# Temp_SMD.net
KiCad netlist of a schematic drawn in EAGLE
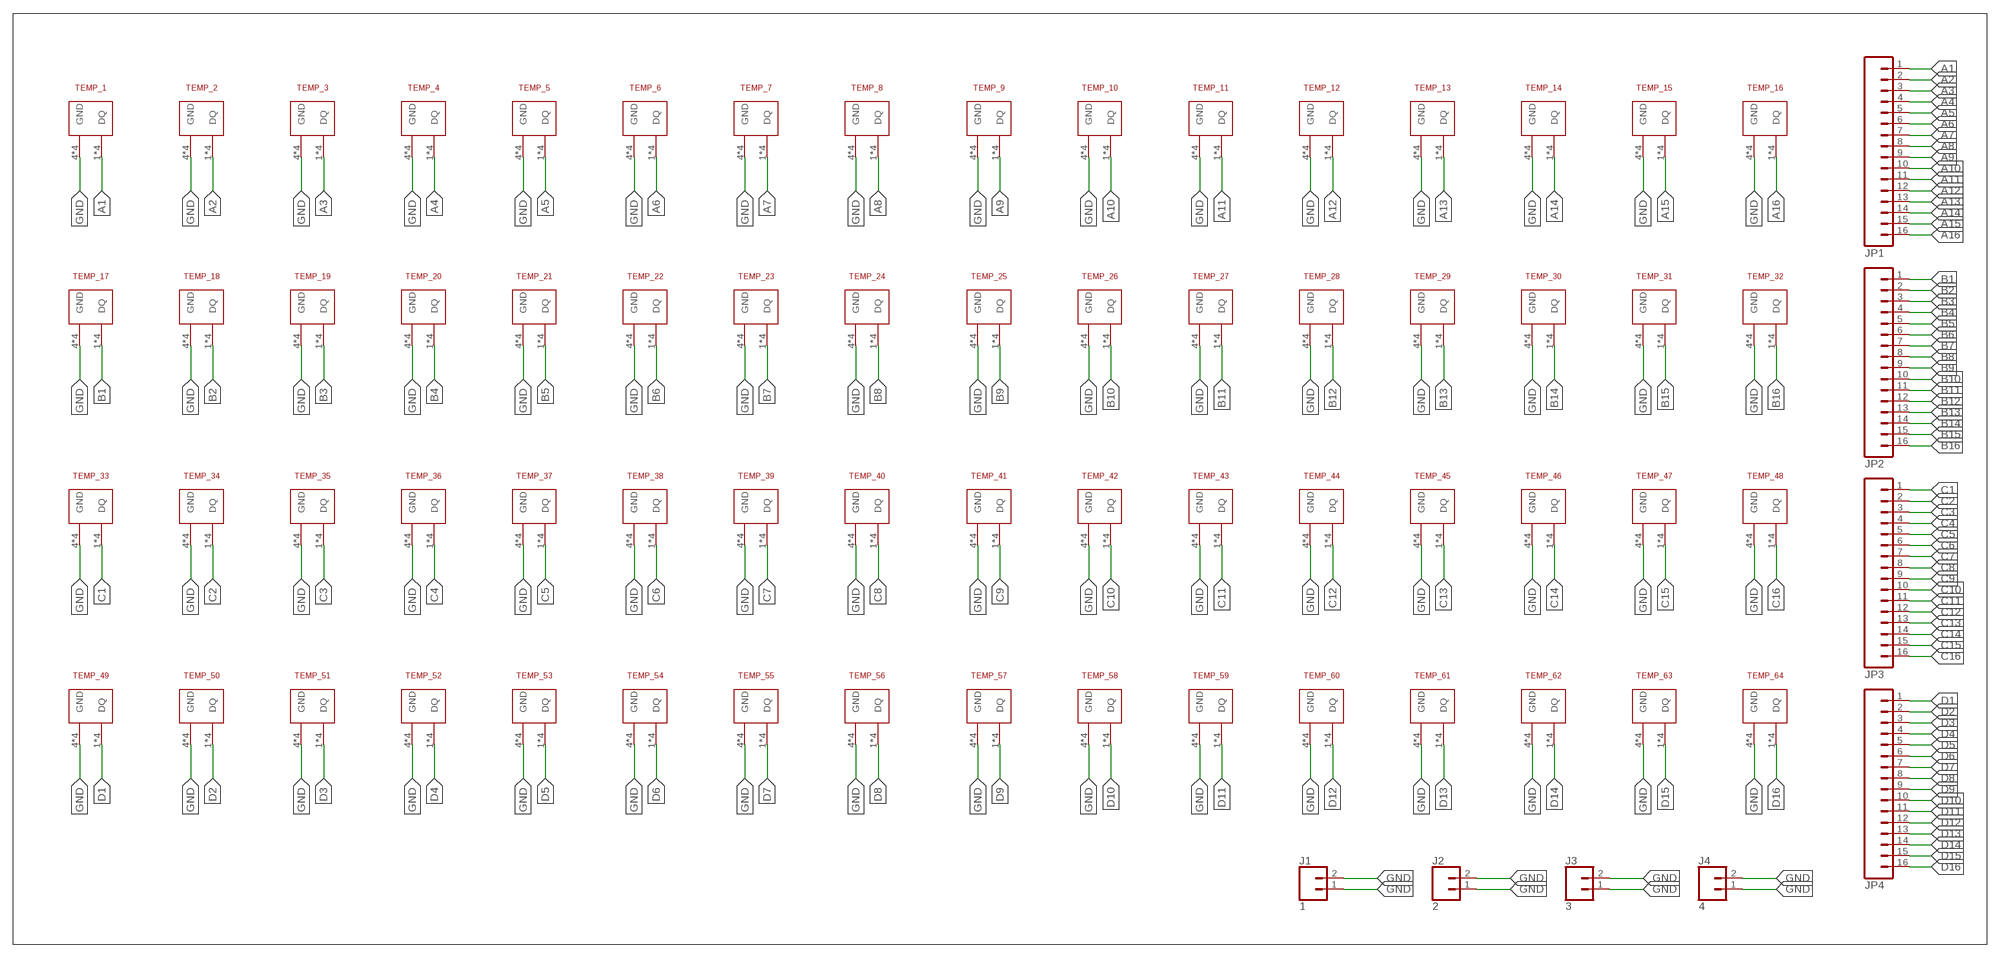
[diagram p0: schematic, sheet 1]

(export (version "E")
  (design (tool "Eeschema 10.0.6"))
  (components
    (comp (ref "J1")
      (value "1")
      (footprint "eagle-import:1X02")
      (libsource (lib "eagle-import") (part "CONN_02"))
    )
    (comp (ref "J2")
      (value "2")
      (footprint "eagle-import:1X02")
      (libsource (lib "eagle-import") (part "CONN_02"))
    )
    (comp (ref "J3")
      (value "3")
      (footprint "eagle-import:1X02")
      (libsource (lib "eagle-import") (part "CONN_02"))
    )
    (comp (ref "J4")
      (value "4")
      (footprint "eagle-import:1X02")
      (libsource (lib "eagle-import") (part "CONN_02"))
    )
    (comp (ref "JP1")
      (value "M16PTH")
      (footprint "eagle-import:1X16")
      (libsource (lib "eagle-import") (part "M16PTH"))
    )
    (comp (ref "JP2")
      (value "M16PTH")
      (footprint "eagle-import:1X16")
      (libsource (lib "eagle-import") (part "M16PTH"))
    )
    (comp (ref "JP3")
      (value "M16PTH")
      (footprint "eagle-import:1X16")
      (libsource (lib "eagle-import") (part "M16PTH"))
    )
    (comp (ref "JP4")
      (value "M16PTH")
      (footprint "eagle-import:1X16")
      (libsource (lib "eagle-import") (part "M16PTH"))
    )
    (comp (ref "TEMP_1")
      (value "SMD_TEMP")
      (footprint "eagle-import:SMD_TEMP")
      (libsource (lib "eagle-import") (part "SMD_TEMP"))
    )
    (comp (ref "TEMP_2")
      (value "SMD_TEMP")
      (footprint "eagle-import:SMD_TEMP")
      (libsource (lib "eagle-import") (part "SMD_TEMP"))
    )
    (comp (ref "TEMP_3")
      (value "SMD_TEMP")
      (footprint "eagle-import:SMD_TEMP")
      (libsource (lib "eagle-import") (part "SMD_TEMP"))
    )
    (comp (ref "TEMP_4")
      (value "SMD_TEMP")
      (footprint "eagle-import:SMD_TEMP")
      (libsource (lib "eagle-import") (part "SMD_TEMP"))
    )
    (comp (ref "TEMP_5")
      (value "SMD_TEMP")
      (footprint "eagle-import:SMD_TEMP")
      (libsource (lib "eagle-import") (part "SMD_TEMP"))
    )
    (comp (ref "TEMP_6")
      (value "SMD_TEMP")
      (footprint "eagle-import:SMD_TEMP")
      (libsource (lib "eagle-import") (part "SMD_TEMP"))
    )
    (comp (ref "TEMP_7")
      (value "SMD_TEMP")
      (footprint "eagle-import:SMD_TEMP")
      (libsource (lib "eagle-import") (part "SMD_TEMP"))
    )
    (comp (ref "TEMP_8")
      (value "SMD_TEMP")
      (footprint "eagle-import:SMD_TEMP")
      (libsource (lib "eagle-import") (part "SMD_TEMP"))
    )
    (comp (ref "TEMP_9")
      (value "SMD_TEMP")
      (footprint "eagle-import:SMD_TEMP")
      (libsource (lib "eagle-import") (part "SMD_TEMP"))
    )
    (comp (ref "TEMP_10")
      (value "SMD_TEMP")
      (footprint "eagle-import:SMD_TEMP")
      (libsource (lib "eagle-import") (part "SMD_TEMP"))
    )
    (comp (ref "TEMP_11")
      (value "SMD_TEMP")
      (footprint "eagle-import:SMD_TEMP")
      (libsource (lib "eagle-import") (part "SMD_TEMP"))
    )
    (comp (ref "TEMP_12")
      (value "SMD_TEMP")
      (footprint "eagle-import:SMD_TEMP")
      (libsource (lib "eagle-import") (part "SMD_TEMP"))
    )
    (comp (ref "TEMP_13")
      (value "SMD_TEMP")
      (footprint "eagle-import:SMD_TEMP")
      (libsource (lib "eagle-import") (part "SMD_TEMP"))
    )
    (comp (ref "TEMP_14")
      (value "SMD_TEMP")
      (footprint "eagle-import:SMD_TEMP")
      (libsource (lib "eagle-import") (part "SMD_TEMP"))
    )
    (comp (ref "TEMP_15")
      (value "SMD_TEMP")
      (footprint "eagle-import:SMD_TEMP")
      (libsource (lib "eagle-import") (part "SMD_TEMP"))
    )
    (comp (ref "TEMP_16")
      (value "SMD_TEMP")
      (footprint "eagle-import:SMD_TEMP")
      (libsource (lib "eagle-import") (part "SMD_TEMP"))
    )
    (comp (ref "TEMP_17")
      (value "SMD_TEMP")
      (footprint "eagle-import:SMD_TEMP")
      (libsource (lib "eagle-import") (part "SMD_TEMP"))
    )
    (comp (ref "TEMP_18")
      (value "SMD_TEMP")
      (footprint "eagle-import:SMD_TEMP")
      (libsource (lib "eagle-import") (part "SMD_TEMP"))
    )
    (comp (ref "TEMP_19")
      (value "SMD_TEMP")
      (footprint "eagle-import:SMD_TEMP")
      (libsource (lib "eagle-import") (part "SMD_TEMP"))
    )
    (comp (ref "TEMP_20")
      (value "SMD_TEMP")
      (footprint "eagle-import:SMD_TEMP")
      (libsource (lib "eagle-import") (part "SMD_TEMP"))
    )
    (comp (ref "TEMP_21")
      (value "SMD_TEMP")
      (footprint "eagle-import:SMD_TEMP")
      (libsource (lib "eagle-import") (part "SMD_TEMP"))
    )
    (comp (ref "TEMP_22")
      (value "SMD_TEMP")
      (footprint "eagle-import:SMD_TEMP")
      (libsource (lib "eagle-import") (part "SMD_TEMP"))
    )
    (comp (ref "TEMP_23")
      (value "SMD_TEMP")
      (footprint "eagle-import:SMD_TEMP")
      (libsource (lib "eagle-import") (part "SMD_TEMP"))
    )
    (comp (ref "TEMP_24")
      (value "SMD_TEMP")
      (footprint "eagle-import:SMD_TEMP")
      (libsource (lib "eagle-import") (part "SMD_TEMP"))
    )
    (comp (ref "TEMP_25")
      (value "SMD_TEMP")
      (footprint "eagle-import:SMD_TEMP")
      (libsource (lib "eagle-import") (part "SMD_TEMP"))
    )
    (comp (ref "TEMP_26")
      (value "SMD_TEMP")
      (footprint "eagle-import:SMD_TEMP")
      (libsource (lib "eagle-import") (part "SMD_TEMP"))
    )
    (comp (ref "TEMP_27")
      (value "SMD_TEMP")
      (footprint "eagle-import:SMD_TEMP")
      (libsource (lib "eagle-import") (part "SMD_TEMP"))
    )
    (comp (ref "TEMP_28")
      (value "SMD_TEMP")
      (footprint "eagle-import:SMD_TEMP")
      (libsource (lib "eagle-import") (part "SMD_TEMP"))
    )
    (comp (ref "TEMP_29")
      (value "SMD_TEMP")
      (footprint "eagle-import:SMD_TEMP")
      (libsource (lib "eagle-import") (part "SMD_TEMP"))
    )
    (comp (ref "TEMP_30")
      (value "SMD_TEMP")
      (footprint "eagle-import:SMD_TEMP")
      (libsource (lib "eagle-import") (part "SMD_TEMP"))
    )
    (comp (ref "TEMP_31")
      (value "SMD_TEMP")
      (footprint "eagle-import:SMD_TEMP")
      (libsource (lib "eagle-import") (part "SMD_TEMP"))
    )
    (comp (ref "TEMP_32")
      (value "SMD_TEMP")
      (footprint "eagle-import:SMD_TEMP")
      (libsource (lib "eagle-import") (part "SMD_TEMP"))
    )
    (comp (ref "TEMP_33")
      (value "SMD_TEMP")
      (footprint "eagle-import:SMD_TEMP")
      (libsource (lib "eagle-import") (part "SMD_TEMP"))
    )
    (comp (ref "TEMP_34")
      (value "SMD_TEMP")
      (footprint "eagle-import:SMD_TEMP")
      (libsource (lib "eagle-import") (part "SMD_TEMP"))
    )
    (comp (ref "TEMP_35")
      (value "SMD_TEMP")
      (footprint "eagle-import:SMD_TEMP")
      (libsource (lib "eagle-import") (part "SMD_TEMP"))
    )
    (comp (ref "TEMP_36")
      (value "SMD_TEMP")
      (footprint "eagle-import:SMD_TEMP")
      (libsource (lib "eagle-import") (part "SMD_TEMP"))
    )
    (comp (ref "TEMP_37")
      (value "SMD_TEMP")
      (footprint "eagle-import:SMD_TEMP")
      (libsource (lib "eagle-import") (part "SMD_TEMP"))
    )
    (comp (ref "TEMP_38")
      (value "SMD_TEMP")
      (footprint "eagle-import:SMD_TEMP")
      (libsource (lib "eagle-import") (part "SMD_TEMP"))
    )
    (comp (ref "TEMP_39")
      (value "SMD_TEMP")
      (footprint "eagle-import:SMD_TEMP")
      (libsource (lib "eagle-import") (part "SMD_TEMP"))
    )
    (comp (ref "TEMP_40")
      (value "SMD_TEMP")
      (footprint "eagle-import:SMD_TEMP")
      (libsource (lib "eagle-import") (part "SMD_TEMP"))
    )
    (comp (ref "TEMP_41")
      (value "SMD_TEMP")
      (footprint "eagle-import:SMD_TEMP")
      (libsource (lib "eagle-import") (part "SMD_TEMP"))
    )
    (comp (ref "TEMP_42")
      (value "SMD_TEMP")
      (footprint "eagle-import:SMD_TEMP")
      (libsource (lib "eagle-import") (part "SMD_TEMP"))
    )
    (comp (ref "TEMP_43")
      (value "SMD_TEMP")
      (footprint "eagle-import:SMD_TEMP")
      (libsource (lib "eagle-import") (part "SMD_TEMP"))
    )
    (comp (ref "TEMP_44")
      (value "SMD_TEMP")
      (footprint "eagle-import:SMD_TEMP")
      (libsource (lib "eagle-import") (part "SMD_TEMP"))
    )
    (comp (ref "TEMP_45")
      (value "SMD_TEMP")
      (footprint "eagle-import:SMD_TEMP")
      (libsource (lib "eagle-import") (part "SMD_TEMP"))
    )
    (comp (ref "TEMP_46")
      (value "SMD_TEMP")
      (footprint "eagle-import:SMD_TEMP")
      (libsource (lib "eagle-import") (part "SMD_TEMP"))
    )
    (comp (ref "TEMP_47")
      (value "SMD_TEMP")
      (footprint "eagle-import:SMD_TEMP")
      (libsource (lib "eagle-import") (part "SMD_TEMP"))
    )
    (comp (ref "TEMP_48")
      (value "SMD_TEMP")
      (footprint "eagle-import:SMD_TEMP")
      (libsource (lib "eagle-import") (part "SMD_TEMP"))
    )
    (comp (ref "TEMP_49")
      (value "SMD_TEMP")
      (footprint "eagle-import:SMD_TEMP")
      (libsource (lib "eagle-import") (part "SMD_TEMP"))
    )
    (comp (ref "TEMP_50")
      (value "SMD_TEMP")
      (footprint "eagle-import:SMD_TEMP")
      (libsource (lib "eagle-import") (part "SMD_TEMP"))
    )
    (comp (ref "TEMP_51")
      (value "SMD_TEMP")
      (footprint "eagle-import:SMD_TEMP")
      (libsource (lib "eagle-import") (part "SMD_TEMP"))
    )
    (comp (ref "TEMP_52")
      (value "SMD_TEMP")
      (footprint "eagle-import:SMD_TEMP")
      (libsource (lib "eagle-import") (part "SMD_TEMP"))
    )
    (comp (ref "TEMP_53")
      (value "SMD_TEMP")
      (footprint "eagle-import:SMD_TEMP")
      (libsource (lib "eagle-import") (part "SMD_TEMP"))
    )
    (comp (ref "TEMP_54")
      (value "SMD_TEMP")
      (footprint "eagle-import:SMD_TEMP")
      (libsource (lib "eagle-import") (part "SMD_TEMP"))
    )
    (comp (ref "TEMP_55")
      (value "SMD_TEMP")
      (footprint "eagle-import:SMD_TEMP")
      (libsource (lib "eagle-import") (part "SMD_TEMP"))
    )
    (comp (ref "TEMP_56")
      (value "SMD_TEMP")
      (footprint "eagle-import:SMD_TEMP")
      (libsource (lib "eagle-import") (part "SMD_TEMP"))
    )
    (comp (ref "TEMP_57")
      (value "SMD_TEMP")
      (footprint "eagle-import:SMD_TEMP")
      (libsource (lib "eagle-import") (part "SMD_TEMP"))
    )
    (comp (ref "TEMP_58")
      (value "SMD_TEMP")
      (footprint "eagle-import:SMD_TEMP")
      (libsource (lib "eagle-import") (part "SMD_TEMP"))
    )
    (comp (ref "TEMP_59")
      (value "SMD_TEMP")
      (footprint "eagle-import:SMD_TEMP")
      (libsource (lib "eagle-import") (part "SMD_TEMP"))
    )
    (comp (ref "TEMP_60")
      (value "SMD_TEMP")
      (footprint "eagle-import:SMD_TEMP")
      (libsource (lib "eagle-import") (part "SMD_TEMP"))
    )
    (comp (ref "TEMP_61")
      (value "SMD_TEMP")
      (footprint "eagle-import:SMD_TEMP")
      (libsource (lib "eagle-import") (part "SMD_TEMP"))
    )
    (comp (ref "TEMP_62")
      (value "SMD_TEMP")
      (footprint "eagle-import:SMD_TEMP")
      (libsource (lib "eagle-import") (part "SMD_TEMP"))
    )
    (comp (ref "TEMP_63")
      (value "SMD_TEMP")
      (footprint "eagle-import:SMD_TEMP")
      (libsource (lib "eagle-import") (part "SMD_TEMP"))
    )
    (comp (ref "TEMP_64")
      (value "SMD_TEMP")
      (footprint "eagle-import:SMD_TEMP")
      (libsource (lib "eagle-import") (part "SMD_TEMP"))
    )
  )
  (nets
    (net (code "1") (name "A1") (class "Default")
      (node (ref "JP1") (pin "1") (pinfunction "1_1") (pintype "passive"))
      (node (ref "TEMP_1") (pin "1") (pinfunction "DQ_1") (pintype "bidirectional"))
      (node (ref "TEMP_1") (pin "DQ") (pinfunction "DQ_DQ") (pintype "bidirectional"))
      (node (ref "TEMP_1") (pin "DQ1") (pinfunction "DQ_DQ1") (pintype "bidirectional"))
      (node (ref "TEMP_1") (pin "DQ2") (pinfunction "DQ_DQ2") (pintype "bidirectional"))
    )
    (net (code "2") (name "A2") (class "Default")
      (node (ref "JP1") (pin "2") (pinfunction "2_2") (pintype "passive"))
      (node (ref "TEMP_2") (pin "1") (pinfunction "DQ_1") (pintype "bidirectional"))
      (node (ref "TEMP_2") (pin "DQ") (pinfunction "DQ_DQ") (pintype "bidirectional"))
      (node (ref "TEMP_2") (pin "DQ1") (pinfunction "DQ_DQ1") (pintype "bidirectional"))
      (node (ref "TEMP_2") (pin "DQ2") (pinfunction "DQ_DQ2") (pintype "bidirectional"))
    )
    (net (code "3") (name "A3") (class "Default")
      (node (ref "JP1") (pin "3") (pinfunction "3_3") (pintype "passive"))
      (node (ref "TEMP_3") (pin "1") (pinfunction "DQ_1") (pintype "bidirectional"))
      (node (ref "TEMP_3") (pin "DQ") (pinfunction "DQ_DQ") (pintype "bidirectional"))
      (node (ref "TEMP_3") (pin "DQ1") (pinfunction "DQ_DQ1") (pintype "bidirectional"))
      (node (ref "TEMP_3") (pin "DQ2") (pinfunction "DQ_DQ2") (pintype "bidirectional"))
    )
    (net (code "4") (name "A4") (class "Default")
      (node (ref "JP1") (pin "4") (pinfunction "4_4") (pintype "passive"))
      (node (ref "TEMP_4") (pin "1") (pinfunction "DQ_1") (pintype "bidirectional"))
      (node (ref "TEMP_4") (pin "DQ") (pinfunction "DQ_DQ") (pintype "bidirectional"))
      (node (ref "TEMP_4") (pin "DQ1") (pinfunction "DQ_DQ1") (pintype "bidirectional"))
      (node (ref "TEMP_4") (pin "DQ2") (pinfunction "DQ_DQ2") (pintype "bidirectional"))
    )
    (net (code "5") (name "A5") (class "Default")
      (node (ref "JP1") (pin "5") (pinfunction "5_5") (pintype "passive"))
      (node (ref "TEMP_5") (pin "1") (pinfunction "DQ_1") (pintype "bidirectional"))
      (node (ref "TEMP_5") (pin "DQ") (pinfunction "DQ_DQ") (pintype "bidirectional"))
      (node (ref "TEMP_5") (pin "DQ1") (pinfunction "DQ_DQ1") (pintype "bidirectional"))
      (node (ref "TEMP_5") (pin "DQ2") (pinfunction "DQ_DQ2") (pintype "bidirectional"))
    )
    (net (code "6") (name "A6") (class "Default")
      (node (ref "JP1") (pin "6") (pinfunction "6_6") (pintype "passive"))
      (node (ref "TEMP_6") (pin "1") (pinfunction "DQ_1") (pintype "bidirectional"))
      (node (ref "TEMP_6") (pin "DQ") (pinfunction "DQ_DQ") (pintype "bidirectional"))
      (node (ref "TEMP_6") (pin "DQ1") (pinfunction "DQ_DQ1") (pintype "bidirectional"))
      (node (ref "TEMP_6") (pin "DQ2") (pinfunction "DQ_DQ2") (pintype "bidirectional"))
    )
    (net (code "7") (name "A7") (class "Default")
      (node (ref "JP1") (pin "7") (pinfunction "7_7") (pintype "passive"))
      (node (ref "TEMP_7") (pin "1") (pinfunction "DQ_1") (pintype "bidirectional"))
      (node (ref "TEMP_7") (pin "DQ") (pinfunction "DQ_DQ") (pintype "bidirectional"))
      (node (ref "TEMP_7") (pin "DQ1") (pinfunction "DQ_DQ1") (pintype "bidirectional"))
      (node (ref "TEMP_7") (pin "DQ2") (pinfunction "DQ_DQ2") (pintype "bidirectional"))
    )
    (net (code "8") (name "A8") (class "Default")
      (node (ref "JP1") (pin "8") (pinfunction "8_8") (pintype "passive"))
      (node (ref "TEMP_8") (pin "1") (pinfunction "DQ_1") (pintype "bidirectional"))
      (node (ref "TEMP_8") (pin "DQ") (pinfunction "DQ_DQ") (pintype "bidirectional"))
      (node (ref "TEMP_8") (pin "DQ1") (pinfunction "DQ_DQ1") (pintype "bidirectional"))
      (node (ref "TEMP_8") (pin "DQ2") (pinfunction "DQ_DQ2") (pintype "bidirectional"))
    )
    (net (code "9") (name "A9") (class "Default")
      (node (ref "JP1") (pin "9") (pinfunction "9_9") (pintype "passive"))
      (node (ref "TEMP_9") (pin "1") (pinfunction "DQ_1") (pintype "bidirectional"))
      (node (ref "TEMP_9") (pin "DQ") (pinfunction "DQ_DQ") (pintype "bidirectional"))
      (node (ref "TEMP_9") (pin "DQ1") (pinfunction "DQ_DQ1") (pintype "bidirectional"))
      (node (ref "TEMP_9") (pin "DQ2") (pinfunction "DQ_DQ2") (pintype "bidirectional"))
    )
    (net (code "10") (name "A10") (class "Default")
      (node (ref "JP1") (pin "10") (pinfunction "10_10") (pintype "passive"))
      (node (ref "TEMP_10") (pin "1") (pinfunction "DQ_1") (pintype "bidirectional"))
      (node (ref "TEMP_10") (pin "DQ") (pinfunction "DQ_DQ") (pintype "bidirectional"))
      (node (ref "TEMP_10") (pin "DQ1") (pinfunction "DQ_DQ1") (pintype "bidirectional"))
      (node (ref "TEMP_10") (pin "DQ2") (pinfunction "DQ_DQ2") (pintype "bidirectional"))
    )
    (net (code "11") (name "A11") (class "Default")
      (node (ref "JP1") (pin "11") (pinfunction "11_11") (pintype "passive"))
      (node (ref "TEMP_11") (pin "1") (pinfunction "DQ_1") (pintype "bidirectional"))
      (node (ref "TEMP_11") (pin "DQ") (pinfunction "DQ_DQ") (pintype "bidirectional"))
      (node (ref "TEMP_11") (pin "DQ1") (pinfunction "DQ_DQ1") (pintype "bidirectional"))
      (node (ref "TEMP_11") (pin "DQ2") (pinfunction "DQ_DQ2") (pintype "bidirectional"))
    )
    (net (code "12") (name "A12") (class "Default")
      (node (ref "JP1") (pin "12") (pinfunction "12_12") (pintype "passive"))
      (node (ref "TEMP_12") (pin "1") (pinfunction "DQ_1") (pintype "bidirectional"))
      (node (ref "TEMP_12") (pin "DQ") (pinfunction "DQ_DQ") (pintype "bidirectional"))
      (node (ref "TEMP_12") (pin "DQ1") (pinfunction "DQ_DQ1") (pintype "bidirectional"))
      (node (ref "TEMP_12") (pin "DQ2") (pinfunction "DQ_DQ2") (pintype "bidirectional"))
    )
    (net (code "13") (name "A13") (class "Default")
      (node (ref "JP1") (pin "13") (pinfunction "13_13") (pintype "passive"))
      (node (ref "TEMP_13") (pin "1") (pinfunction "DQ_1") (pintype "bidirectional"))
      (node (ref "TEMP_13") (pin "DQ") (pinfunction "DQ_DQ") (pintype "bidirectional"))
      (node (ref "TEMP_13") (pin "DQ1") (pinfunction "DQ_DQ1") (pintype "bidirectional"))
      (node (ref "TEMP_13") (pin "DQ2") (pinfunction "DQ_DQ2") (pintype "bidirectional"))
    )
    (net (code "14") (name "A14") (class "Default")
      (node (ref "JP1") (pin "14") (pinfunction "14_14") (pintype "passive"))
      (node (ref "TEMP_14") (pin "1") (pinfunction "DQ_1") (pintype "bidirectional"))
      (node (ref "TEMP_14") (pin "DQ") (pinfunction "DQ_DQ") (pintype "bidirectional"))
      (node (ref "TEMP_14") (pin "DQ1") (pinfunction "DQ_DQ1") (pintype "bidirectional"))
      (node (ref "TEMP_14") (pin "DQ2") (pinfunction "DQ_DQ2") (pintype "bidirectional"))
    )
    (net (code "15") (name "A15") (class "Default")
      (node (ref "JP1") (pin "15") (pinfunction "15_15") (pintype "passive"))
      (node (ref "TEMP_15") (pin "1") (pinfunction "DQ_1") (pintype "bidirectional"))
      (node (ref "TEMP_15") (pin "DQ") (pinfunction "DQ_DQ") (pintype "bidirectional"))
      (node (ref "TEMP_15") (pin "DQ1") (pinfunction "DQ_DQ1") (pintype "bidirectional"))
      (node (ref "TEMP_15") (pin "DQ2") (pinfunction "DQ_DQ2") (pintype "bidirectional"))
    )
    (net (code "16") (name "A16") (class "Default")
      (node (ref "JP1") (pin "16") (pinfunction "16_16") (pintype "passive"))
      (node (ref "TEMP_16") (pin "1") (pinfunction "DQ_1") (pintype "bidirectional"))
      (node (ref "TEMP_16") (pin "DQ") (pinfunction "DQ_DQ") (pintype "bidirectional"))
      (node (ref "TEMP_16") (pin "DQ1") (pinfunction "DQ_DQ1") (pintype "bidirectional"))
      (node (ref "TEMP_16") (pin "DQ2") (pinfunction "DQ_DQ2") (pintype "bidirectional"))
    )
    (net (code "17") (name "B1") (class "Default")
      (node (ref "JP2") (pin "1") (pinfunction "1_1") (pintype "passive"))
      (node (ref "TEMP_17") (pin "1") (pinfunction "DQ_1") (pintype "bidirectional"))
      (node (ref "TEMP_17") (pin "DQ") (pinfunction "DQ_DQ") (pintype "bidirectional"))
      (node (ref "TEMP_17") (pin "DQ1") (pinfunction "DQ_DQ1") (pintype "bidirectional"))
      (node (ref "TEMP_17") (pin "DQ2") (pinfunction "DQ_DQ2") (pintype "bidirectional"))
    )
    (net (code "18") (name "B2") (class "Default")
      (node (ref "JP2") (pin "2") (pinfunction "2_2") (pintype "passive"))
      (node (ref "TEMP_18") (pin "1") (pinfunction "DQ_1") (pintype "bidirectional"))
      (node (ref "TEMP_18") (pin "DQ") (pinfunction "DQ_DQ") (pintype "bidirectional"))
      (node (ref "TEMP_18") (pin "DQ1") (pinfunction "DQ_DQ1") (pintype "bidirectional"))
      (node (ref "TEMP_18") (pin "DQ2") (pinfunction "DQ_DQ2") (pintype "bidirectional"))
    )
    (net (code "19") (name "B3") (class "Default")
      (node (ref "JP2") (pin "3") (pinfunction "3_3") (pintype "passive"))
      (node (ref "TEMP_19") (pin "1") (pinfunction "DQ_1") (pintype "bidirectional"))
      (node (ref "TEMP_19") (pin "DQ") (pinfunction "DQ_DQ") (pintype "bidirectional"))
      (node (ref "TEMP_19") (pin "DQ1") (pinfunction "DQ_DQ1") (pintype "bidirectional"))
      (node (ref "TEMP_19") (pin "DQ2") (pinfunction "DQ_DQ2") (pintype "bidirectional"))
    )
    (net (code "20") (name "B4") (class "Default")
      (node (ref "JP2") (pin "4") (pinfunction "4_4") (pintype "passive"))
      (node (ref "TEMP_20") (pin "1") (pinfunction "DQ_1") (pintype "bidirectional"))
      (node (ref "TEMP_20") (pin "DQ") (pinfunction "DQ_DQ") (pintype "bidirectional"))
      (node (ref "TEMP_20") (pin "DQ1") (pinfunction "DQ_DQ1") (pintype "bidirectional"))
      (node (ref "TEMP_20") (pin "DQ2") (pinfunction "DQ_DQ2") (pintype "bidirectional"))
    )
    (net (code "21") (name "B5") (class "Default")
      (node (ref "JP2") (pin "5") (pinfunction "5_5") (pintype "passive"))
      (node (ref "TEMP_21") (pin "1") (pinfunction "DQ_1") (pintype "bidirectional"))
      (node (ref "TEMP_21") (pin "DQ") (pinfunction "DQ_DQ") (pintype "bidirectional"))
      (node (ref "TEMP_21") (pin "DQ1") (pinfunction "DQ_DQ1") (pintype "bidirectional"))
      (node (ref "TEMP_21") (pin "DQ2") (pinfunction "DQ_DQ2") (pintype "bidirectional"))
    )
    (net (code "22") (name "B6") (class "Default")
      (node (ref "JP2") (pin "6") (pinfunction "6_6") (pintype "passive"))
      (node (ref "TEMP_22") (pin "1") (pinfunction "DQ_1") (pintype "bidirectional"))
      (node (ref "TEMP_22") (pin "DQ") (pinfunction "DQ_DQ") (pintype "bidirectional"))
      (node (ref "TEMP_22") (pin "DQ1") (pinfunction "DQ_DQ1") (pintype "bidirectional"))
      (node (ref "TEMP_22") (pin "DQ2") (pinfunction "DQ_DQ2") (pintype "bidirectional"))
    )
    (net (code "23") (name "B7") (class "Default")
      (node (ref "JP2") (pin "7") (pinfunction "7_7") (pintype "passive"))
      (node (ref "TEMP_23") (pin "1") (pinfunction "DQ_1") (pintype "bidirectional"))
      (node (ref "TEMP_23") (pin "DQ") (pinfunction "DQ_DQ") (pintype "bidirectional"))
      (node (ref "TEMP_23") (pin "DQ1") (pinfunction "DQ_DQ1") (pintype "bidirectional"))
      (node (ref "TEMP_23") (pin "DQ2") (pinfunction "DQ_DQ2") (pintype "bidirectional"))
    )
    (net (code "24") (name "B8") (class "Default")
      (node (ref "JP2") (pin "8") (pinfunction "8_8") (pintype "passive"))
      (node (ref "TEMP_24") (pin "1") (pinfunction "DQ_1") (pintype "bidirectional"))
      (node (ref "TEMP_24") (pin "DQ") (pinfunction "DQ_DQ") (pintype "bidirectional"))
      (node (ref "TEMP_24") (pin "DQ1") (pinfunction "DQ_DQ1") (pintype "bidirectional"))
      (node (ref "TEMP_24") (pin "DQ2") (pinfunction "DQ_DQ2") (pintype "bidirectional"))
    )
    (net (code "25") (name "B9") (class "Default")
      (node (ref "JP2") (pin "9") (pinfunction "9_9") (pintype "passive"))
      (node (ref "TEMP_25") (pin "1") (pinfunction "DQ_1") (pintype "bidirectional"))
      (node (ref "TEMP_25") (pin "DQ") (pinfunction "DQ_DQ") (pintype "bidirectional"))
      (node (ref "TEMP_25") (pin "DQ1") (pinfunction "DQ_DQ1") (pintype "bidirectional"))
      (node (ref "TEMP_25") (pin "DQ2") (pinfunction "DQ_DQ2") (pintype "bidirectional"))
    )
    (net (code "26") (name "B10") (class "Default")
      (node (ref "JP2") (pin "10") (pinfunction "10_10") (pintype "passive"))
      (node (ref "TEMP_26") (pin "1") (pinfunction "DQ_1") (pintype "bidirectional"))
      (node (ref "TEMP_26") (pin "DQ") (pinfunction "DQ_DQ") (pintype "bidirectional"))
      (node (ref "TEMP_26") (pin "DQ1") (pinfunction "DQ_DQ1") (pintype "bidirectional"))
      (node (ref "TEMP_26") (pin "DQ2") (pinfunction "DQ_DQ2") (pintype "bidirectional"))
    )
    (net (code "27") (name "B11") (class "Default")
      (node (ref "JP2") (pin "11") (pinfunction "11_11") (pintype "passive"))
      (node (ref "TEMP_27") (pin "1") (pinfunction "DQ_1") (pintype "bidirectional"))
      (node (ref "TEMP_27") (pin "DQ") (pinfunction "DQ_DQ") (pintype "bidirectional"))
      (node (ref "TEMP_27") (pin "DQ1") (pinfunction "DQ_DQ1") (pintype "bidirectional"))
      (node (ref "TEMP_27") (pin "DQ2") (pinfunction "DQ_DQ2") (pintype "bidirectional"))
    )
    (net (code "28") (name "B12") (class "Default")
      (node (ref "JP2") (pin "12") (pinfunction "12_12") (pintype "passive"))
      (node (ref "TEMP_28") (pin "1") (pinfunction "DQ_1") (pintype "bidirectional"))
      (node (ref "TEMP_28") (pin "DQ") (pinfunction "DQ_DQ") (pintype "bidirectional"))
      (node (ref "TEMP_28") (pin "DQ1") (pinfunction "DQ_DQ1") (pintype "bidirectional"))
      (node (ref "TEMP_28") (pin "DQ2") (pinfunction "DQ_DQ2") (pintype "bidirectional"))
    )
    (net (code "29") (name "B13") (class "Default")
      (node (ref "JP2") (pin "13") (pinfunction "13_13") (pintype "passive"))
      (node (ref "TEMP_29") (pin "1") (pinfunction "DQ_1") (pintype "bidirectional"))
      (node (ref "TEMP_29") (pin "DQ") (pinfunction "DQ_DQ") (pintype "bidirectional"))
      (node (ref "TEMP_29") (pin "DQ1") (pinfunction "DQ_DQ1") (pintype "bidirectional"))
      (node (ref "TEMP_29") (pin "DQ2") (pinfunction "DQ_DQ2") (pintype "bidirectional"))
    )
    (net (code "30") (name "B14") (class "Default")
      (node (ref "JP2") (pin "14") (pinfunction "14_14") (pintype "passive"))
      (node (ref "TEMP_30") (pin "1") (pinfunction "DQ_1") (pintype "bidirectional"))
      (node (ref "TEMP_30") (pin "DQ") (pinfunction "DQ_DQ") (pintype "bidirectional"))
      (node (ref "TEMP_30") (pin "DQ1") (pinfunction "DQ_DQ1") (pintype "bidirectional"))
      (node (ref "TEMP_30") (pin "DQ2") (pinfunction "DQ_DQ2") (pintype "bidirectional"))
    )
    (net (code "31") (name "B15") (class "Default")
      (node (ref "JP2") (pin "15") (pinfunction "15_15") (pintype "passive"))
      (node (ref "TEMP_31") (pin "1") (pinfunction "DQ_1") (pintype "bidirectional"))
      (node (ref "TEMP_31") (pin "DQ") (pinfunction "DQ_DQ") (pintype "bidirectional"))
      (node (ref "TEMP_31") (pin "DQ1") (pinfunction "DQ_DQ1") (pintype "bidirectional"))
      (node (ref "TEMP_31") (pin "DQ2") (pinfunction "DQ_DQ2") (pintype "bidirectional"))
    )
    (net (code "32") (name "B16") (class "Default")
      (node (ref "JP2") (pin "16") (pinfunction "16_16") (pintype "passive"))
      (node (ref "TEMP_32") (pin "1") (pinfunction "DQ_1") (pintype "bidirectional"))
      (node (ref "TEMP_32") (pin "DQ") (pinfunction "DQ_DQ") (pintype "bidirectional"))
      (node (ref "TEMP_32") (pin "DQ1") (pinfunction "DQ_DQ1") (pintype "bidirectional"))
      (node (ref "TEMP_32") (pin "DQ2") (pinfunction "DQ_DQ2") (pintype "bidirectional"))
    )
    (net (code "33") (name "C1") (class "Default")
      (node (ref "JP3") (pin "1") (pinfunction "1_1") (pintype "passive"))
      (node (ref "TEMP_33") (pin "1") (pinfunction "DQ_1") (pintype "bidirectional"))
      (node (ref "TEMP_33") (pin "DQ") (pinfunction "DQ_DQ") (pintype "bidirectional"))
      (node (ref "TEMP_33") (pin "DQ1") (pinfunction "DQ_DQ1") (pintype "bidirectional"))
      (node (ref "TEMP_33") (pin "DQ2") (pinfunction "DQ_DQ2") (pintype "bidirectional"))
    )
    (net (code "34") (name "C2") (class "Default")
      (node (ref "JP3") (pin "2") (pinfunction "2_2") (pintype "passive"))
      (node (ref "TEMP_34") (pin "1") (pinfunction "DQ_1") (pintype "bidirectional"))
      (node (ref "TEMP_34") (pin "DQ") (pinfunction "DQ_DQ") (pintype "bidirectional"))
      (node (ref "TEMP_34") (pin "DQ1") (pinfunction "DQ_DQ1") (pintype "bidirectional"))
      (node (ref "TEMP_34") (pin "DQ2") (pinfunction "DQ_DQ2") (pintype "bidirectional"))
    )
    (net (code "35") (name "C3") (class "Default")
      (node (ref "JP3") (pin "3") (pinfunction "3_3") (pintype "passive"))
      (node (ref "TEMP_35") (pin "1") (pinfunction "DQ_1") (pintype "bidirectional"))
      (node (ref "TEMP_35") (pin "DQ") (pinfunction "DQ_DQ") (pintype "bidirectional"))
      (node (ref "TEMP_35") (pin "DQ1") (pinfunction "DQ_DQ1") (pintype "bidirectional"))
      (node (ref "TEMP_35") (pin "DQ2") (pinfunction "DQ_DQ2") (pintype "bidirectional"))
    )
    (net (code "36") (name "C4") (class "Default")
      (node (ref "JP3") (pin "4") (pinfunction "4_4") (pintype "passive"))
      (node (ref "TEMP_36") (pin "1") (pinfunction "DQ_1") (pintype "bidirectional"))
      (node (ref "TEMP_36") (pin "DQ") (pinfunction "DQ_DQ") (pintype "bidirectional"))
      (node (ref "TEMP_36") (pin "DQ1") (pinfunction "DQ_DQ1") (pintype "bidirectional"))
      (node (ref "TEMP_36") (pin "DQ2") (pinfunction "DQ_DQ2") (pintype "bidirectional"))
    )
    (net (code "37") (name "C5") (class "Default")
      (node (ref "JP3") (pin "5") (pinfunction "5_5") (pintype "passive"))
      (node (ref "TEMP_37") (pin "1") (pinfunction "DQ_1") (pintype "bidirectional"))
      (node (ref "TEMP_37") (pin "DQ") (pinfunction "DQ_DQ") (pintype "bidirectional"))
      (node (ref "TEMP_37") (pin "DQ1") (pinfunction "DQ_DQ1") (pintype "bidirectional"))
      (node (ref "TEMP_37") (pin "DQ2") (pinfunction "DQ_DQ2") (pintype "bidirectional"))
    )
    (net (code "38") (name "C6") (class "Default")
      (node (ref "JP3") (pin "6") (pinfunction "6_6") (pintype "passive"))
      (node (ref "TEMP_38") (pin "1") (pinfunction "DQ_1") (pintype "bidirectional"))
      (node (ref "TEMP_38") (pin "DQ") (pinfunction "DQ_DQ") (pintype "bidirectional"))
      (node (ref "TEMP_38") (pin "DQ1") (pinfunction "DQ_DQ1") (pintype "bidirectional"))
      (node (ref "TEMP_38") (pin "DQ2") (pinfunction "DQ_DQ2") (pintype "bidirectional"))
    )
    (net (code "39") (name "C7") (class "Default")
      (node (ref "JP3") (pin "7") (pinfunction "7_7") (pintype "passive"))
      (node (ref "TEMP_39") (pin "1") (pinfunction "DQ_1") (pintype "bidirectional"))
      (node (ref "TEMP_39") (pin "DQ") (pinfunction "DQ_DQ") (pintype "bidirectional"))
      (node (ref "TEMP_39") (pin "DQ1") (pinfunction "DQ_DQ1") (pintype "bidirectional"))
      (node (ref "TEMP_39") (pin "DQ2") (pinfunction "DQ_DQ2") (pintype "bidirectional"))
    )
    (net (code "40") (name "C8") (class "Default")
      (node (ref "JP3") (pin "8") (pinfunction "8_8") (pintype "passive"))
      (node (ref "TEMP_40") (pin "1") (pinfunction "DQ_1") (pintype "bidirectional"))
      (node (ref "TEMP_40") (pin "DQ") (pinfunction "DQ_DQ") (pintype "bidirectional"))
      (node (ref "TEMP_40") (pin "DQ1") (pinfunction "DQ_DQ1") (pintype "bidirectional"))
      (node (ref "TEMP_40") (pin "DQ2") (pinfunction "DQ_DQ2") (pintype "bidirectional"))
    )
    (net (code "41") (name "C9") (class "Default")
      (node (ref "JP3") (pin "9") (pinfunction "9_9") (pintype "passive"))
      (node (ref "TEMP_41") (pin "1") (pinfunction "DQ_1") (pintype "bidirectional"))
      (node (ref "TEMP_41") (pin "DQ") (pinfunction "DQ_DQ") (pintype "bidirectional"))
      (node (ref "TEMP_41") (pin "DQ1") (pinfunction "DQ_DQ1") (pintype "bidirectional"))
      (node (ref "TEMP_41") (pin "DQ2") (pinfunction "DQ_DQ2") (pintype "bidirectional"))
    )
    (net (code "42") (name "C10") (class "Default")
      (node (ref "JP3") (pin "10") (pinfunction "10_10") (pintype "passive"))
      (node (ref "TEMP_42") (pin "1") (pinfunction "DQ_1") (pintype "bidirectional"))
      (node (ref "TEMP_42") (pin "DQ") (pinfunction "DQ_DQ") (pintype "bidirectional"))
      (node (ref "TEMP_42") (pin "DQ1") (pinfunction "DQ_DQ1") (pintype "bidirectional"))
      (node (ref "TEMP_42") (pin "DQ2") (pinfunction "DQ_DQ2") (pintype "bidirectional"))
    )
    (net (code "43") (name "C11") (class "Default")
      (node (ref "JP3") (pin "11") (pinfunction "11_11") (pintype "passive"))
      (node (ref "TEMP_43") (pin "1") (pinfunction "DQ_1") (pintype "bidirectional"))
      (node (ref "TEMP_43") (pin "DQ") (pinfunction "DQ_DQ") (pintype "bidirectional"))
      (node (ref "TEMP_43") (pin "DQ1") (pinfunction "DQ_DQ1") (pintype "bidirectional"))
      (node (ref "TEMP_43") (pin "DQ2") (pinfunction "DQ_DQ2") (pintype "bidirectional"))
    )
    (net (code "44") (name "C12") (class "Default")
      (node (ref "JP3") (pin "12") (pinfunction "12_12") (pintype "passive"))
      (node (ref "TEMP_44") (pin "1") (pinfunction "DQ_1") (pintype "bidirectional"))
      (node (ref "TEMP_44") (pin "DQ") (pinfunction "DQ_DQ") (pintype "bidirectional"))
      (node (ref "TEMP_44") (pin "DQ1") (pinfunction "DQ_DQ1") (pintype "bidirectional"))
      (node (ref "TEMP_44") (pin "DQ2") (pinfunction "DQ_DQ2") (pintype "bidirectional"))
    )
    (net (code "45") (name "C13") (class "Default")
      (node (ref "JP3") (pin "13") (pinfunction "13_13") (pintype "passive"))
      (node (ref "TEMP_45") (pin "1") (pinfunction "DQ_1") (pintype "bidirectional"))
      (node (ref "TEMP_45") (pin "DQ") (pinfunction "DQ_DQ") (pintype "bidirectional"))
      (node (ref "TEMP_45") (pin "DQ1") (pinfunction "DQ_DQ1") (pintype "bidirectional"))
      (node (ref "TEMP_45") (pin "DQ2") (pinfunction "DQ_DQ2") (pintype "bidirectional"))
    )
    (net (code "46") (name "C14") (class "Default")
      (node (ref "JP3") (pin "14") (pinfunction "14_14") (pintype "passive"))
      (node (ref "TEMP_46") (pin "1") (pinfunction "DQ_1") (pintype "bidirectional"))
      (node (ref "TEMP_46") (pin "DQ") (pinfunction "DQ_DQ") (pintype "bidirectional"))
      (node (ref "TEMP_46") (pin "DQ1") (pinfunction "DQ_DQ1") (pintype "bidirectional"))
      (node (ref "TEMP_46") (pin "DQ2") (pinfunction "DQ_DQ2") (pintype "bidirectional"))
    )
    (net (code "47") (name "C15") (class "Default")
      (node (ref "JP3") (pin "15") (pinfunction "15_15") (pintype "passive"))
      (node (ref "TEMP_47") (pin "1") (pinfunction "DQ_1") (pintype "bidirectional"))
      (node (ref "TEMP_47") (pin "DQ") (pinfunction "DQ_DQ") (pintype "bidirectional"))
      (node (ref "TEMP_47") (pin "DQ1") (pinfunction "DQ_DQ1") (pintype "bidirectional"))
      (node (ref "TEMP_47") (pin "DQ2") (pinfunction "DQ_DQ2") (pintype "bidirectional"))
    )
    (net (code "48") (name "C16") (class "Default")
      (node (ref "JP3") (pin "16") (pinfunction "16_16") (pintype "passive"))
      (node (ref "TEMP_48") (pin "1") (pinfunction "DQ_1") (pintype "bidirectional"))
      (node (ref "TEMP_48") (pin "DQ") (pinfunction "DQ_DQ") (pintype "bidirectional"))
      (node (ref "TEMP_48") (pin "DQ1") (pinfunction "DQ_DQ1") (pintype "bidirectional"))
      (node (ref "TEMP_48") (pin "DQ2") (pinfunction "DQ_DQ2") (pintype "bidirectional"))
    )
    (net (code "49") (name "D1") (class "Default")
      (node (ref "JP4") (pin "1") (pinfunction "1_1") (pintype "passive"))
      (node (ref "TEMP_49") (pin "1") (pinfunction "DQ_1") (pintype "bidirectional"))
      (node (ref "TEMP_49") (pin "DQ") (pinfunction "DQ_DQ") (pintype "bidirectional"))
      (node (ref "TEMP_49") (pin "DQ1") (pinfunction "DQ_DQ1") (pintype "bidirectional"))
      (node (ref "TEMP_49") (pin "DQ2") (pinfunction "DQ_DQ2") (pintype "bidirectional"))
    )
    (net (code "50") (name "D2") (class "Default")
      (node (ref "JP4") (pin "2") (pinfunction "2_2") (pintype "passive"))
      (node (ref "TEMP_50") (pin "1") (pinfunction "DQ_1") (pintype "bidirectional"))
      (node (ref "TEMP_50") (pin "DQ") (pinfunction "DQ_DQ") (pintype "bidirectional"))
      (node (ref "TEMP_50") (pin "DQ1") (pinfunction "DQ_DQ1") (pintype "bidirectional"))
      (node (ref "TEMP_50") (pin "DQ2") (pinfunction "DQ_DQ2") (pintype "bidirectional"))
    )
    (net (code "51") (name "D3") (class "Default")
      (node (ref "JP4") (pin "3") (pinfunction "3_3") (pintype "passive"))
      (node (ref "TEMP_51") (pin "1") (pinfunction "DQ_1") (pintype "bidirectional"))
      (node (ref "TEMP_51") (pin "DQ") (pinfunction "DQ_DQ") (pintype "bidirectional"))
      (node (ref "TEMP_51") (pin "DQ1") (pinfunction "DQ_DQ1") (pintype "bidirectional"))
      (node (ref "TEMP_51") (pin "DQ2") (pinfunction "DQ_DQ2") (pintype "bidirectional"))
    )
    (net (code "52") (name "D4") (class "Default")
      (node (ref "JP4") (pin "4") (pinfunction "4_4") (pintype "passive"))
      (node (ref "TEMP_52") (pin "1") (pinfunction "DQ_1") (pintype "bidirectional"))
      (node (ref "TEMP_52") (pin "DQ") (pinfunction "DQ_DQ") (pintype "bidirectional"))
      (node (ref "TEMP_52") (pin "DQ1") (pinfunction "DQ_DQ1") (pintype "bidirectional"))
      (node (ref "TEMP_52") (pin "DQ2") (pinfunction "DQ_DQ2") (pintype "bidirectional"))
    )
    (net (code "53") (name "D5") (class "Default")
      (node (ref "JP4") (pin "5") (pinfunction "5_5") (pintype "passive"))
      (node (ref "TEMP_53") (pin "1") (pinfunction "DQ_1") (pintype "bidirectional"))
      (node (ref "TEMP_53") (pin "DQ") (pinfunction "DQ_DQ") (pintype "bidirectional"))
      (node (ref "TEMP_53") (pin "DQ1") (pinfunction "DQ_DQ1") (pintype "bidirectional"))
      (node (ref "TEMP_53") (pin "DQ2") (pinfunction "DQ_DQ2") (pintype "bidirectional"))
    )
    (net (code "54") (name "D6") (class "Default")
      (node (ref "JP4") (pin "6") (pinfunction "6_6") (pintype "passive"))
      (node (ref "TEMP_54") (pin "1") (pinfunction "DQ_1") (pintype "bidirectional"))
      (node (ref "TEMP_54") (pin "DQ") (pinfunction "DQ_DQ") (pintype "bidirectional"))
      (node (ref "TEMP_54") (pin "DQ1") (pinfunction "DQ_DQ1") (pintype "bidirectional"))
      (node (ref "TEMP_54") (pin "DQ2") (pinfunction "DQ_DQ2") (pintype "bidirectional"))
    )
    (net (code "55") (name "D7") (class "Default")
      (node (ref "JP4") (pin "7") (pinfunction "7_7") (pintype "passive"))
      (node (ref "TEMP_55") (pin "1") (pinfunction "DQ_1") (pintype "bidirectional"))
      (node (ref "TEMP_55") (pin "DQ") (pinfunction "DQ_DQ") (pintype "bidirectional"))
      (node (ref "TEMP_55") (pin "DQ1") (pinfunction "DQ_DQ1") (pintype "bidirectional"))
      (node (ref "TEMP_55") (pin "DQ2") (pinfunction "DQ_DQ2") (pintype "bidirectional"))
    )
    (net (code "56") (name "D8") (class "Default")
      (node (ref "JP4") (pin "8") (pinfunction "8_8") (pintype "passive"))
      (node (ref "TEMP_56") (pin "1") (pinfunction "DQ_1") (pintype "bidirectional"))
      (node (ref "TEMP_56") (pin "DQ") (pinfunction "DQ_DQ") (pintype "bidirectional"))
      (node (ref "TEMP_56") (pin "DQ1") (pinfunction "DQ_DQ1") (pintype "bidirectional"))
      (node (ref "TEMP_56") (pin "DQ2") (pinfunction "DQ_DQ2") (pintype "bidirectional"))
    )
    (net (code "57") (name "D9") (class "Default")
      (node (ref "JP4") (pin "9") (pinfunction "9_9") (pintype "passive"))
      (node (ref "TEMP_57") (pin "1") (pinfunction "DQ_1") (pintype "bidirectional"))
      (node (ref "TEMP_57") (pin "DQ") (pinfunction "DQ_DQ") (pintype "bidirectional"))
      (node (ref "TEMP_57") (pin "DQ1") (pinfunction "DQ_DQ1") (pintype "bidirectional"))
      (node (ref "TEMP_57") (pin "DQ2") (pinfunction "DQ_DQ2") (pintype "bidirectional"))
    )
    (net (code "58") (name "D10") (class "Default")
      (node (ref "JP4") (pin "10") (pinfunction "10_10") (pintype "passive"))
      (node (ref "TEMP_58") (pin "1") (pinfunction "DQ_1") (pintype "bidirectional"))
      (node (ref "TEMP_58") (pin "DQ") (pinfunction "DQ_DQ") (pintype "bidirectional"))
      (node (ref "TEMP_58") (pin "DQ1") (pinfunction "DQ_DQ1") (pintype "bidirectional"))
      (node (ref "TEMP_58") (pin "DQ2") (pinfunction "DQ_DQ2") (pintype "bidirectional"))
    )
    (net (code "59") (name "D11") (class "Default")
      (node (ref "JP4") (pin "11") (pinfunction "11_11") (pintype "passive"))
      (node (ref "TEMP_59") (pin "1") (pinfunction "DQ_1") (pintype "bidirectional"))
      (node (ref "TEMP_59") (pin "DQ") (pinfunction "DQ_DQ") (pintype "bidirectional"))
      (node (ref "TEMP_59") (pin "DQ1") (pinfunction "DQ_DQ1") (pintype "bidirectional"))
      (node (ref "TEMP_59") (pin "DQ2") (pinfunction "DQ_DQ2") (pintype "bidirectional"))
    )
    (net (code "60") (name "D12") (class "Default")
      (node (ref "JP4") (pin "12") (pinfunction "12_12") (pintype "passive"))
      (node (ref "TEMP_60") (pin "1") (pinfunction "DQ_1") (pintype "bidirectional"))
      (node (ref "TEMP_60") (pin "DQ") (pinfunction "DQ_DQ") (pintype "bidirectional"))
      (node (ref "TEMP_60") (pin "DQ1") (pinfunction "DQ_DQ1") (pintype "bidirectional"))
      (node (ref "TEMP_60") (pin "DQ2") (pinfunction "DQ_DQ2") (pintype "bidirectional"))
    )
    (net (code "61") (name "D13") (class "Default")
      (node (ref "JP4") (pin "13") (pinfunction "13_13") (pintype "passive"))
      (node (ref "TEMP_61") (pin "1") (pinfunction "DQ_1") (pintype "bidirectional"))
      (node (ref "TEMP_61") (pin "DQ") (pinfunction "DQ_DQ") (pintype "bidirectional"))
      (node (ref "TEMP_61") (pin "DQ1") (pinfunction "DQ_DQ1") (pintype "bidirectional"))
      (node (ref "TEMP_61") (pin "DQ2") (pinfunction "DQ_DQ2") (pintype "bidirectional"))
    )
    (net (code "62") (name "D14") (class "Default")
      (node (ref "JP4") (pin "14") (pinfunction "14_14") (pintype "passive"))
      (node (ref "TEMP_62") (pin "1") (pinfunction "DQ_1") (pintype "bidirectional"))
      (node (ref "TEMP_62") (pin "DQ") (pinfunction "DQ_DQ") (pintype "bidirectional"))
      (node (ref "TEMP_62") (pin "DQ1") (pinfunction "DQ_DQ1") (pintype "bidirectional"))
      (node (ref "TEMP_62") (pin "DQ2") (pinfunction "DQ_DQ2") (pintype "bidirectional"))
    )
    (net (code "63") (name "D15") (class "Default")
      (node (ref "JP4") (pin "15") (pinfunction "15_15") (pintype "passive"))
      (node (ref "TEMP_63") (pin "1") (pinfunction "DQ_1") (pintype "bidirectional"))
      (node (ref "TEMP_63") (pin "DQ") (pinfunction "DQ_DQ") (pintype "bidirectional"))
      (node (ref "TEMP_63") (pin "DQ1") (pinfunction "DQ_DQ1") (pintype "bidirectional"))
      (node (ref "TEMP_63") (pin "DQ2") (pinfunction "DQ_DQ2") (pintype "bidirectional"))
    )
    (net (code "64") (name "D16") (class "Default")
      (node (ref "JP4") (pin "16") (pinfunction "16_16") (pintype "passive"))
      (node (ref "TEMP_64") (pin "1") (pinfunction "DQ_1") (pintype "bidirectional"))
      (node (ref "TEMP_64") (pin "DQ") (pinfunction "DQ_DQ") (pintype "bidirectional"))
      (node (ref "TEMP_64") (pin "DQ1") (pinfunction "DQ_DQ1") (pintype "bidirectional"))
      (node (ref "TEMP_64") (pin "DQ2") (pinfunction "DQ_DQ2") (pintype "bidirectional"))
    )
    (net (code "65") (name "GND") (class "Default")
      (node (ref "J1") (pin "1") (pinfunction "1_1") (pintype "passive"))
      (node (ref "J1") (pin "2") (pinfunction "2_2") (pintype "passive"))
      (node (ref "J2") (pin "1") (pinfunction "1_1") (pintype "passive"))
      (node (ref "J2") (pin "2") (pinfunction "2_2") (pintype "passive"))
      (node (ref "J3") (pin "1") (pinfunction "1_1") (pintype "passive"))
      (node (ref "J3") (pin "2") (pinfunction "2_2") (pintype "passive"))
      (node (ref "J4") (pin "1") (pinfunction "1_1") (pintype "passive"))
      (node (ref "J4") (pin "2") (pinfunction "2_2") (pintype "passive"))
      (node (ref "TEMP_1") (pin "4") (pinfunction "GND_4") (pintype "bidirectional"))
      (node (ref "TEMP_1") (pin "8") (pinfunction "GND_8") (pintype "bidirectional"))
      (node (ref "TEMP_1") (pin "GND1") (pinfunction "GND_GND1") (pintype "bidirectional"))
      (node (ref "TEMP_1") (pin "GND2") (pinfunction "GND_GND2") (pintype "bidirectional"))
      (node (ref "TEMP_10") (pin "4") (pinfunction "GND_4") (pintype "bidirectional"))
      (node (ref "TEMP_10") (pin "8") (pinfunction "GND_8") (pintype "bidirectional"))
      (node (ref "TEMP_10") (pin "GND1") (pinfunction "GND_GND1") (pintype "bidirectional"))
      (node (ref "TEMP_10") (pin "GND2") (pinfunction "GND_GND2") (pintype "bidirectional"))
      (node (ref "TEMP_11") (pin "4") (pinfunction "GND_4") (pintype "bidirectional"))
      (node (ref "TEMP_11") (pin "8") (pinfunction "GND_8") (pintype "bidirectional"))
      (node (ref "TEMP_11") (pin "GND1") (pinfunction "GND_GND1") (pintype "bidirectional"))
      (node (ref "TEMP_11") (pin "GND2") (pinfunction "GND_GND2") (pintype "bidirectional"))
      (node (ref "TEMP_12") (pin "4") (pinfunction "GND_4") (pintype "bidirectional"))
      (node (ref "TEMP_12") (pin "8") (pinfunction "GND_8") (pintype "bidirectional"))
      (node (ref "TEMP_12") (pin "GND1") (pinfunction "GND_GND1") (pintype "bidirectional"))
      (node (ref "TEMP_12") (pin "GND2") (pinfunction "GND_GND2") (pintype "bidirectional"))
      (node (ref "TEMP_13") (pin "4") (pinfunction "GND_4") (pintype "bidirectional"))
      (node (ref "TEMP_13") (pin "8") (pinfunction "GND_8") (pintype "bidirectional"))
      (node (ref "TEMP_13") (pin "GND1") (pinfunction "GND_GND1") (pintype "bidirectional"))
      (node (ref "TEMP_13") (pin "GND2") (pinfunction "GND_GND2") (pintype "bidirectional"))
      (node (ref "TEMP_14") (pin "4") (pinfunction "GND_4") (pintype "bidirectional"))
      (node (ref "TEMP_14") (pin "8") (pinfunction "GND_8") (pintype "bidirectional"))
      (node (ref "TEMP_14") (pin "GND1") (pinfunction "GND_GND1") (pintype "bidirectional"))
      (node (ref "TEMP_14") (pin "GND2") (pinfunction "GND_GND2") (pintype "bidirectional"))
      (node (ref "TEMP_15") (pin "4") (pinfunction "GND_4") (pintype "bidirectional"))
      (node (ref "TEMP_15") (pin "8") (pinfunction "GND_8") (pintype "bidirectional"))
      (node (ref "TEMP_15") (pin "GND1") (pinfunction "GND_GND1") (pintype "bidirectional"))
      (node (ref "TEMP_15") (pin "GND2") (pinfunction "GND_GND2") (pintype "bidirectional"))
      (node (ref "TEMP_16") (pin "4") (pinfunction "GND_4") (pintype "bidirectional"))
      (node (ref "TEMP_16") (pin "8") (pinfunction "GND_8") (pintype "bidirectional"))
      (node (ref "TEMP_16") (pin "GND1") (pinfunction "GND_GND1") (pintype "bidirectional"))
      (node (ref "TEMP_16") (pin "GND2") (pinfunction "GND_GND2") (pintype "bidirectional"))
      (node (ref "TEMP_17") (pin "4") (pinfunction "GND_4") (pintype "bidirectional"))
      (node (ref "TEMP_17") (pin "8") (pinfunction "GND_8") (pintype "bidirectional"))
      (node (ref "TEMP_17") (pin "GND1") (pinfunction "GND_GND1") (pintype "bidirectional"))
      (node (ref "TEMP_17") (pin "GND2") (pinfunction "GND_GND2") (pintype "bidirectional"))
      (node (ref "TEMP_18") (pin "4") (pinfunction "GND_4") (pintype "bidirectional"))
      (node (ref "TEMP_18") (pin "8") (pinfunction "GND_8") (pintype "bidirectional"))
      (node (ref "TEMP_18") (pin "GND1") (pinfunction "GND_GND1") (pintype "bidirectional"))
      (node (ref "TEMP_18") (pin "GND2") (pinfunction "GND_GND2") (pintype "bidirectional"))
      (node (ref "TEMP_19") (pin "4") (pinfunction "GND_4") (pintype "bidirectional"))
      (node (ref "TEMP_19") (pin "8") (pinfunction "GND_8") (pintype "bidirectional"))
      (node (ref "TEMP_19") (pin "GND1") (pinfunction "GND_GND1") (pintype "bidirectional"))
      (node (ref "TEMP_19") (pin "GND2") (pinfunction "GND_GND2") (pintype "bidirectional"))
      (node (ref "TEMP_2") (pin "4") (pinfunction "GND_4") (pintype "bidirectional"))
      (node (ref "TEMP_2") (pin "8") (pinfunction "GND_8") (pintype "bidirectional"))
      (node (ref "TEMP_2") (pin "GND1") (pinfunction "GND_GND1") (pintype "bidirectional"))
      (node (ref "TEMP_2") (pin "GND2") (pinfunction "GND_GND2") (pintype "bidirectional"))
      (node (ref "TEMP_20") (pin "4") (pinfunction "GND_4") (pintype "bidirectional"))
      (node (ref "TEMP_20") (pin "8") (pinfunction "GND_8") (pintype "bidirectional"))
      (node (ref "TEMP_20") (pin "GND1") (pinfunction "GND_GND1") (pintype "bidirectional"))
      (node (ref "TEMP_20") (pin "GND2") (pinfunction "GND_GND2") (pintype "bidirectional"))
      (node (ref "TEMP_21") (pin "4") (pinfunction "GND_4") (pintype "bidirectional"))
      (node (ref "TEMP_21") (pin "8") (pinfunction "GND_8") (pintype "bidirectional"))
      (node (ref "TEMP_21") (pin "GND1") (pinfunction "GND_GND1") (pintype "bidirectional"))
      (node (ref "TEMP_21") (pin "GND2") (pinfunction "GND_GND2") (pintype "bidirectional"))
      (node (ref "TEMP_22") (pin "4") (pinfunction "GND_4") (pintype "bidirectional"))
      (node (ref "TEMP_22") (pin "8") (pinfunction "GND_8") (pintype "bidirectional"))
      (node (ref "TEMP_22") (pin "GND1") (pinfunction "GND_GND1") (pintype "bidirectional"))
      (node (ref "TEMP_22") (pin "GND2") (pinfunction "GND_GND2") (pintype "bidirectional"))
      (node (ref "TEMP_23") (pin "4") (pinfunction "GND_4") (pintype "bidirectional"))
      (node (ref "TEMP_23") (pin "8") (pinfunction "GND_8") (pintype "bidirectional"))
      (node (ref "TEMP_23") (pin "GND1") (pinfunction "GND_GND1") (pintype "bidirectional"))
      (node (ref "TEMP_23") (pin "GND2") (pinfunction "GND_GND2") (pintype "bidirectional"))
      (node (ref "TEMP_24") (pin "4") (pinfunction "GND_4") (pintype "bidirectional"))
      (node (ref "TEMP_24") (pin "8") (pinfunction "GND_8") (pintype "bidirectional"))
      (node (ref "TEMP_24") (pin "GND1") (pinfunction "GND_GND1") (pintype "bidirectional"))
      (node (ref "TEMP_24") (pin "GND2") (pinfunction "GND_GND2") (pintype "bidirectional"))
      (node (ref "TEMP_25") (pin "4") (pinfunction "GND_4") (pintype "bidirectional"))
      (node (ref "TEMP_25") (pin "8") (pinfunction "GND_8") (pintype "bidirectional"))
      (node (ref "TEMP_25") (pin "GND1") (pinfunction "GND_GND1") (pintype "bidirectional"))
      (node (ref "TEMP_25") (pin "GND2") (pinfunction "GND_GND2") (pintype "bidirectional"))
      (node (ref "TEMP_26") (pin "4") (pinfunction "GND_4") (pintype "bidirectional"))
      (node (ref "TEMP_26") (pin "8") (pinfunction "GND_8") (pintype "bidirectional"))
      (node (ref "TEMP_26") (pin "GND1") (pinfunction "GND_GND1") (pintype "bidirectional"))
      (node (ref "TEMP_26") (pin "GND2") (pinfunction "GND_GND2") (pintype "bidirectional"))
      (node (ref "TEMP_27") (pin "4") (pinfunction "GND_4") (pintype "bidirectional"))
      (node (ref "TEMP_27") (pin "8") (pinfunction "GND_8") (pintype "bidirectional"))
      (node (ref "TEMP_27") (pin "GND1") (pinfunction "GND_GND1") (pintype "bidirectional"))
      (node (ref "TEMP_27") (pin "GND2") (pinfunction "GND_GND2") (pintype "bidirectional"))
      (node (ref "TEMP_28") (pin "4") (pinfunction "GND_4") (pintype "bidirectional"))
      (node (ref "TEMP_28") (pin "8") (pinfunction "GND_8") (pintype "bidirectional"))
      (node (ref "TEMP_28") (pin "GND1") (pinfunction "GND_GND1") (pintype "bidirectional"))
      (node (ref "TEMP_28") (pin "GND2") (pinfunction "GND_GND2") (pintype "bidirectional"))
      (node (ref "TEMP_29") (pin "4") (pinfunction "GND_4") (pintype "bidirectional"))
      (node (ref "TEMP_29") (pin "8") (pinfunction "GND_8") (pintype "bidirectional"))
      (node (ref "TEMP_29") (pin "GND1") (pinfunction "GND_GND1") (pintype "bidirectional"))
      (node (ref "TEMP_29") (pin "GND2") (pinfunction "GND_GND2") (pintype "bidirectional"))
      (node (ref "TEMP_3") (pin "4") (pinfunction "GND_4") (pintype "bidirectional"))
      (node (ref "TEMP_3") (pin "8") (pinfunction "GND_8") (pintype "bidirectional"))
      (node (ref "TEMP_3") (pin "GND1") (pinfunction "GND_GND1") (pintype "bidirectional"))
      (node (ref "TEMP_3") (pin "GND2") (pinfunction "GND_GND2") (pintype "bidirectional"))
      (node (ref "TEMP_30") (pin "4") (pinfunction "GND_4") (pintype "bidirectional"))
      (node (ref "TEMP_30") (pin "8") (pinfunction "GND_8") (pintype "bidirectional"))
      (node (ref "TEMP_30") (pin "GND1") (pinfunction "GND_GND1") (pintype "bidirectional"))
      (node (ref "TEMP_30") (pin "GND2") (pinfunction "GND_GND2") (pintype "bidirectional"))
      (node (ref "TEMP_31") (pin "4") (pinfunction "GND_4") (pintype "bidirectional"))
      (node (ref "TEMP_31") (pin "8") (pinfunction "GND_8") (pintype "bidirectional"))
      (node (ref "TEMP_31") (pin "GND1") (pinfunction "GND_GND1") (pintype "bidirectional"))
      (node (ref "TEMP_31") (pin "GND2") (pinfunction "GND_GND2") (pintype "bidirectional"))
      (node (ref "TEMP_32") (pin "4") (pinfunction "GND_4") (pintype "bidirectional"))
      (node (ref "TEMP_32") (pin "8") (pinfunction "GND_8") (pintype "bidirectional"))
      (node (ref "TEMP_32") (pin "GND1") (pinfunction "GND_GND1") (pintype "bidirectional"))
      (node (ref "TEMP_32") (pin "GND2") (pinfunction "GND_GND2") (pintype "bidirectional"))
      (node (ref "TEMP_33") (pin "4") (pinfunction "GND_4") (pintype "bidirectional"))
      (node (ref "TEMP_33") (pin "8") (pinfunction "GND_8") (pintype "bidirectional"))
      (node (ref "TEMP_33") (pin "GND1") (pinfunction "GND_GND1") (pintype "bidirectional"))
      (node (ref "TEMP_33") (pin "GND2") (pinfunction "GND_GND2") (pintype "bidirectional"))
      (node (ref "TEMP_34") (pin "4") (pinfunction "GND_4") (pintype "bidirectional"))
      (node (ref "TEMP_34") (pin "8") (pinfunction "GND_8") (pintype "bidirectional"))
      (node (ref "TEMP_34") (pin "GND1") (pinfunction "GND_GND1") (pintype "bidirectional"))
      (node (ref "TEMP_34") (pin "GND2") (pinfunction "GND_GND2") (pintype "bidirectional"))
      (node (ref "TEMP_35") (pin "4") (pinfunction "GND_4") (pintype "bidirectional"))
      (node (ref "TEMP_35") (pin "8") (pinfunction "GND_8") (pintype "bidirectional"))
      (node (ref "TEMP_35") (pin "GND1") (pinfunction "GND_GND1") (pintype "bidirectional"))
      (node (ref "TEMP_35") (pin "GND2") (pinfunction "GND_GND2") (pintype "bidirectional"))
      (node (ref "TEMP_36") (pin "4") (pinfunction "GND_4") (pintype "bidirectional"))
      (node (ref "TEMP_36") (pin "8") (pinfunction "GND_8") (pintype "bidirectional"))
      (node (ref "TEMP_36") (pin "GND1") (pinfunction "GND_GND1") (pintype "bidirectional"))
      (node (ref "TEMP_36") (pin "GND2") (pinfunction "GND_GND2") (pintype "bidirectional"))
      (node (ref "TEMP_37") (pin "4") (pinfunction "GND_4") (pintype "bidirectional"))
      (node (ref "TEMP_37") (pin "8") (pinfunction "GND_8") (pintype "bidirectional"))
      (node (ref "TEMP_37") (pin "GND1") (pinfunction "GND_GND1") (pintype "bidirectional"))
      (node (ref "TEMP_37") (pin "GND2") (pinfunction "GND_GND2") (pintype "bidirectional"))
      (node (ref "TEMP_38") (pin "4") (pinfunction "GND_4") (pintype "bidirectional"))
      (node (ref "TEMP_38") (pin "8") (pinfunction "GND_8") (pintype "bidirectional"))
      (node (ref "TEMP_38") (pin "GND1") (pinfunction "GND_GND1") (pintype "bidirectional"))
      (node (ref "TEMP_38") (pin "GND2") (pinfunction "GND_GND2") (pintype "bidirectional"))
      (node (ref "TEMP_39") (pin "4") (pinfunction "GND_4") (pintype "bidirectional"))
      (node (ref "TEMP_39") (pin "8") (pinfunction "GND_8") (pintype "bidirectional"))
      (node (ref "TEMP_39") (pin "GND1") (pinfunction "GND_GND1") (pintype "bidirectional"))
      (node (ref "TEMP_39") (pin "GND2") (pinfunction "GND_GND2") (pintype "bidirectional"))
      (node (ref "TEMP_4") (pin "4") (pinfunction "GND_4") (pintype "bidirectional"))
      (node (ref "TEMP_4") (pin "8") (pinfunction "GND_8") (pintype "bidirectional"))
      (node (ref "TEMP_4") (pin "GND1") (pinfunction "GND_GND1") (pintype "bidirectional"))
      (node (ref "TEMP_4") (pin "GND2") (pinfunction "GND_GND2") (pintype "bidirectional"))
      (node (ref "TEMP_40") (pin "4") (pinfunction "GND_4") (pintype "bidirectional"))
      (node (ref "TEMP_40") (pin "8") (pinfunction "GND_8") (pintype "bidirectional"))
      (node (ref "TEMP_40") (pin "GND1") (pinfunction "GND_GND1") (pintype "bidirectional"))
      (node (ref "TEMP_40") (pin "GND2") (pinfunction "GND_GND2") (pintype "bidirectional"))
      (node (ref "TEMP_41") (pin "4") (pinfunction "GND_4") (pintype "bidirectional"))
      (node (ref "TEMP_41") (pin "8") (pinfunction "GND_8") (pintype "bidirectional"))
      (node (ref "TEMP_41") (pin "GND1") (pinfunction "GND_GND1") (pintype "bidirectional"))
      (node (ref "TEMP_41") (pin "GND2") (pinfunction "GND_GND2") (pintype "bidirectional"))
      (node (ref "TEMP_42") (pin "4") (pinfunction "GND_4") (pintype "bidirectional"))
      (node (ref "TEMP_42") (pin "8") (pinfunction "GND_8") (pintype "bidirectional"))
      (node (ref "TEMP_42") (pin "GND1") (pinfunction "GND_GND1") (pintype "bidirectional"))
      (node (ref "TEMP_42") (pin "GND2") (pinfunction "GND_GND2") (pintype "bidirectional"))
      (node (ref "TEMP_43") (pin "4") (pinfunction "GND_4") (pintype "bidirectional"))
      (node (ref "TEMP_43") (pin "8") (pinfunction "GND_8") (pintype "bidirectional"))
      (node (ref "TEMP_43") (pin "GND1") (pinfunction "GND_GND1") (pintype "bidirectional"))
      (node (ref "TEMP_43") (pin "GND2") (pinfunction "GND_GND2") (pintype "bidirectional"))
      (node (ref "TEMP_44") (pin "4") (pinfunction "GND_4") (pintype "bidirectional"))
      (node (ref "TEMP_44") (pin "8") (pinfunction "GND_8") (pintype "bidirectional"))
      (node (ref "TEMP_44") (pin "GND1") (pinfunction "GND_GND1") (pintype "bidirectional"))
      (node (ref "TEMP_44") (pin "GND2") (pinfunction "GND_GND2") (pintype "bidirectional"))
      (node (ref "TEMP_45") (pin "4") (pinfunction "GND_4") (pintype "bidirectional"))
      (node (ref "TEMP_45") (pin "8") (pinfunction "GND_8") (pintype "bidirectional"))
      (node (ref "TEMP_45") (pin "GND1") (pinfunction "GND_GND1") (pintype "bidirectional"))
      (node (ref "TEMP_45") (pin "GND2") (pinfunction "GND_GND2") (pintype "bidirectional"))
      (node (ref "TEMP_46") (pin "4") (pinfunction "GND_4") (pintype "bidirectional"))
      (node (ref "TEMP_46") (pin "8") (pinfunction "GND_8") (pintype "bidirectional"))
      (node (ref "TEMP_46") (pin "GND1") (pinfunction "GND_GND1") (pintype "bidirectional"))
      (node (ref "TEMP_46") (pin "GND2") (pinfunction "GND_GND2") (pintype "bidirectional"))
      (node (ref "TEMP_47") (pin "4") (pinfunction "GND_4") (pintype "bidirectional"))
      (node (ref "TEMP_47") (pin "8") (pinfunction "GND_8") (pintype "bidirectional"))
      (node (ref "TEMP_47") (pin "GND1") (pinfunction "GND_GND1") (pintype "bidirectional"))
      (node (ref "TEMP_47") (pin "GND2") (pinfunction "GND_GND2") (pintype "bidirectional"))
      (node (ref "TEMP_48") (pin "4") (pinfunction "GND_4") (pintype "bidirectional"))
      (node (ref "TEMP_48") (pin "8") (pinfunction "GND_8") (pintype "bidirectional"))
      (node (ref "TEMP_48") (pin "GND1") (pinfunction "GND_GND1") (pintype "bidirectional"))
      (node (ref "TEMP_48") (pin "GND2") (pinfunction "GND_GND2") (pintype "bidirectional"))
      (node (ref "TEMP_49") (pin "4") (pinfunction "GND_4") (pintype "bidirectional"))
      (node (ref "TEMP_49") (pin "8") (pinfunction "GND_8") (pintype "bidirectional"))
      (node (ref "TEMP_49") (pin "GND1") (pinfunction "GND_GND1") (pintype "bidirectional"))
      (node (ref "TEMP_49") (pin "GND2") (pinfunction "GND_GND2") (pintype "bidirectional"))
      (node (ref "TEMP_5") (pin "4") (pinfunction "GND_4") (pintype "bidirectional"))
      (node (ref "TEMP_5") (pin "8") (pinfunction "GND_8") (pintype "bidirectional"))
      (node (ref "TEMP_5") (pin "GND1") (pinfunction "GND_GND1") (pintype "bidirectional"))
      (node (ref "TEMP_5") (pin "GND2") (pinfunction "GND_GND2") (pintype "bidirectional"))
      (node (ref "TEMP_50") (pin "4") (pinfunction "GND_4") (pintype "bidirectional"))
      (node (ref "TEMP_50") (pin "8") (pinfunction "GND_8") (pintype "bidirectional"))
      (node (ref "TEMP_50") (pin "GND1") (pinfunction "GND_GND1") (pintype "bidirectional"))
      (node (ref "TEMP_50") (pin "GND2") (pinfunction "GND_GND2") (pintype "bidirectional"))
      (node (ref "TEMP_51") (pin "4") (pinfunction "GND_4") (pintype "bidirectional"))
      (node (ref "TEMP_51") (pin "8") (pinfunction "GND_8") (pintype "bidirectional"))
      (node (ref "TEMP_51") (pin "GND1") (pinfunction "GND_GND1") (pintype "bidirectional"))
      (node (ref "TEMP_51") (pin "GND2") (pinfunction "GND_GND2") (pintype "bidirectional"))
      (node (ref "TEMP_52") (pin "4") (pinfunction "GND_4") (pintype "bidirectional"))
      (node (ref "TEMP_52") (pin "8") (pinfunction "GND_8") (pintype "bidirectional"))
      (node (ref "TEMP_52") (pin "GND1") (pinfunction "GND_GND1") (pintype "bidirectional"))
      (node (ref "TEMP_52") (pin "GND2") (pinfunction "GND_GND2") (pintype "bidirectional"))
      (node (ref "TEMP_53") (pin "4") (pinfunction "GND_4") (pintype "bidirectional"))
      (node (ref "TEMP_53") (pin "8") (pinfunction "GND_8") (pintype "bidirectional"))
      (node (ref "TEMP_53") (pin "GND1") (pinfunction "GND_GND1") (pintype "bidirectional"))
      (node (ref "TEMP_53") (pin "GND2") (pinfunction "GND_GND2") (pintype "bidirectional"))
      (node (ref "TEMP_54") (pin "4") (pinfunction "GND_4") (pintype "bidirectional"))
      (node (ref "TEMP_54") (pin "8") (pinfunction "GND_8") (pintype "bidirectional"))
      (node (ref "TEMP_54") (pin "GND1") (pinfunction "GND_GND1") (pintype "bidirectional"))
      (node (ref "TEMP_54") (pin "GND2") (pinfunction "GND_GND2") (pintype "bidirectional"))
      (node (ref "TEMP_55") (pin "4") (pinfunction "GND_4") (pintype "bidirectional"))
      (node (ref "TEMP_55") (pin "8") (pinfunction "GND_8") (pintype "bidirectional"))
      (node (ref "TEMP_55") (pin "GND1") (pinfunction "GND_GND1") (pintype "bidirectional"))
      (node (ref "TEMP_55") (pin "GND2") (pinfunction "GND_GND2") (pintype "bidirectional"))
      (node (ref "TEMP_56") (pin "4") (pinfunction "GND_4") (pintype "bidirectional"))
      (node (ref "TEMP_56") (pin "8") (pinfunction "GND_8") (pintype "bidirectional"))
      (node (ref "TEMP_56") (pin "GND1") (pinfunction "GND_GND1") (pintype "bidirectional"))
      (node (ref "TEMP_56") (pin "GND2") (pinfunction "GND_GND2") (pintype "bidirectional"))
      (node (ref "TEMP_57") (pin "4") (pinfunction "GND_4") (pintype "bidirectional"))
      (node (ref "TEMP_57") (pin "8") (pinfunction "GND_8") (pintype "bidirectional"))
      (node (ref "TEMP_57") (pin "GND1") (pinfunction "GND_GND1") (pintype "bidirectional"))
      (node (ref "TEMP_57") (pin "GND2") (pinfunction "GND_GND2") (pintype "bidirectional"))
      (node (ref "TEMP_58") (pin "4") (pinfunction "GND_4") (pintype "bidirectional"))
      (node (ref "TEMP_58") (pin "8") (pinfunction "GND_8") (pintype "bidirectional"))
      (node (ref "TEMP_58") (pin "GND1") (pinfunction "GND_GND1") (pintype "bidirectional"))
      (node (ref "TEMP_58") (pin "GND2") (pinfunction "GND_GND2") (pintype "bidirectional"))
      (node (ref "TEMP_59") (pin "4") (pinfunction "GND_4") (pintype "bidirectional"))
      (node (ref "TEMP_59") (pin "8") (pinfunction "GND_8") (pintype "bidirectional"))
      (node (ref "TEMP_59") (pin "GND1") (pinfunction "GND_GND1") (pintype "bidirectional"))
      (node (ref "TEMP_59") (pin "GND2") (pinfunction "GND_GND2") (pintype "bidirectional"))
      (node (ref "TEMP_6") (pin "4") (pinfunction "GND_4") (pintype "bidirectional"))
      (node (ref "TEMP_6") (pin "8") (pinfunction "GND_8") (pintype "bidirectional"))
      (node (ref "TEMP_6") (pin "GND1") (pinfunction "GND_GND1") (pintype "bidirectional"))
      (node (ref "TEMP_6") (pin "GND2") (pinfunction "GND_GND2") (pintype "bidirectional"))
      (node (ref "TEMP_60") (pin "4") (pinfunction "GND_4") (pintype "bidirectional"))
      (node (ref "TEMP_60") (pin "8") (pinfunction "GND_8") (pintype "bidirectional"))
      (node (ref "TEMP_60") (pin "GND1") (pinfunction "GND_GND1") (pintype "bidirectional"))
      (node (ref "TEMP_60") (pin "GND2") (pinfunction "GND_GND2") (pintype "bidirectional"))
      (node (ref "TEMP_61") (pin "4") (pinfunction "GND_4") (pintype "bidirectional"))
      (node (ref "TEMP_61") (pin "8") (pinfunction "GND_8") (pintype "bidirectional"))
      (node (ref "TEMP_61") (pin "GND1") (pinfunction "GND_GND1") (pintype "bidirectional"))
      (node (ref "TEMP_61") (pin "GND2") (pinfunction "GND_GND2") (pintype "bidirectional"))
      (node (ref "TEMP_62") (pin "4") (pinfunction "GND_4") (pintype "bidirectional"))
      (node (ref "TEMP_62") (pin "8") (pinfunction "GND_8") (pintype "bidirectional"))
      (node (ref "TEMP_62") (pin "GND1") (pinfunction "GND_GND1") (pintype "bidirectional"))
      (node (ref "TEMP_62") (pin "GND2") (pinfunction "GND_GND2") (pintype "bidirectional"))
      (node (ref "TEMP_63") (pin "4") (pinfunction "GND_4") (pintype "bidirectional"))
      (node (ref "TEMP_63") (pin "8") (pinfunction "GND_8") (pintype "bidirectional"))
      (node (ref "TEMP_63") (pin "GND1") (pinfunction "GND_GND1") (pintype "bidirectional"))
      (node (ref "TEMP_63") (pin "GND2") (pinfunction "GND_GND2") (pintype "bidirectional"))
      (node (ref "TEMP_64") (pin "4") (pinfunction "GND_4") (pintype "bidirectional"))
      (node (ref "TEMP_64") (pin "8") (pinfunction "GND_8") (pintype "bidirectional"))
      (node (ref "TEMP_64") (pin "GND1") (pinfunction "GND_GND1") (pintype "bidirectional"))
      (node (ref "TEMP_64") (pin "GND2") (pinfunction "GND_GND2") (pintype "bidirectional"))
      (node (ref "TEMP_7") (pin "4") (pinfunction "GND_4") (pintype "bidirectional"))
      (node (ref "TEMP_7") (pin "8") (pinfunction "GND_8") (pintype "bidirectional"))
      (node (ref "TEMP_7") (pin "GND1") (pinfunction "GND_GND1") (pintype "bidirectional"))
      (node (ref "TEMP_7") (pin "GND2") (pinfunction "GND_GND2") (pintype "bidirectional"))
      (node (ref "TEMP_8") (pin "4") (pinfunction "GND_4") (pintype "bidirectional"))
      (node (ref "TEMP_8") (pin "8") (pinfunction "GND_8") (pintype "bidirectional"))
      (node (ref "TEMP_8") (pin "GND1") (pinfunction "GND_GND1") (pintype "bidirectional"))
      (node (ref "TEMP_8") (pin "GND2") (pinfunction "GND_GND2") (pintype "bidirectional"))
      (node (ref "TEMP_9") (pin "4") (pinfunction "GND_4") (pintype "bidirectional"))
      (node (ref "TEMP_9") (pin "8") (pinfunction "GND_8") (pintype "bidirectional"))
      (node (ref "TEMP_9") (pin "GND1") (pinfunction "GND_GND1") (pintype "bidirectional"))
      (node (ref "TEMP_9") (pin "GND2") (pinfunction "GND_GND2") (pintype "bidirectional"))
    )
  )
)
